# hello-world.net
KiCad netlist of a schematic drawn in EAGLE
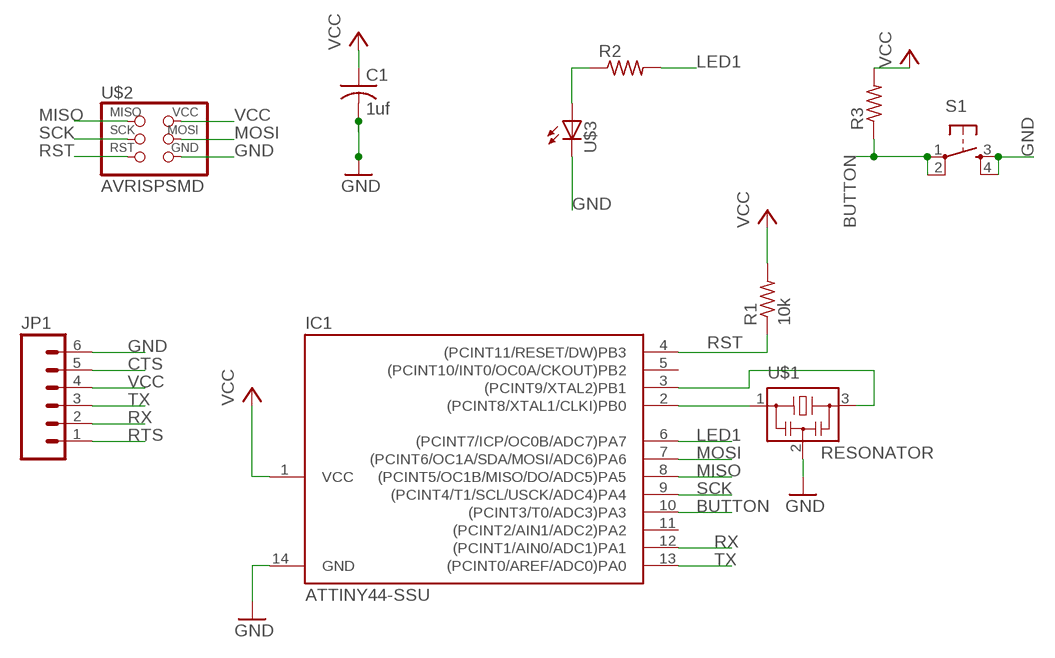
[diagram p0: schematic, sheet 1]

(export (version "E")
  (design (tool "Eeschema 10.0.6"))
  (components
    (comp (ref "C1")
      (value "1uf")
      (footprint "eagle-import:C1206")
      (libsource (lib "eagle-import") (part "C-USC1206"))
    )
    (comp (ref "IC1")
      (value "ATTINY44-SSU")
      (footprint "eagle-import:SOIC14")
      (libsource (lib "eagle-import") (part "ATTINY44-SSU"))
    )
    (comp (ref "JP1")
      (value "M06SMD")
      (footprint "eagle-import:1X06-SMD")
      (libsource (lib "eagle-import") (part "M06SMD"))
    )
    (comp (ref "R1")
      (value "10k")
      (footprint "eagle-import:R1206")
      (libsource (lib "eagle-import") (part "R-US_R1206"))
    )
    (comp (ref "R2")
      (value "RESISTOR1206")
      (footprint "eagle-import:1206")
      (libsource (lib "eagle-import") (part "RESISTOR1206"))
    )
    (comp (ref "R3")
      (value "RESISTOR1206")
      (footprint "eagle-import:1206")
      (libsource (lib "eagle-import") (part "RESISTOR1206"))
    )
    (comp (ref "S1")
      (value "6MM_SWITCH6MM_SWITCH")
      (footprint "eagle-import:6MM_SWITCH")
      (libsource (lib "eagle-import") (part "6MM_SWITCH6MM_SWITCH"))
    )
    (comp (ref "U$1")
      (value "RESONATOR")
      (footprint "eagle-import:EFOBM")
      (libsource (lib "eagle-import") (part "RESONATOR"))
    )
    (comp (ref "U$2")
      (value "AVRISPSMD")
      (footprint "eagle-import:2X03SMD")
      (libsource (lib "eagle-import") (part "AVRISPSMD"))
    )
    (comp (ref "U$3")
      (value "LED1206")
      (footprint "eagle-import:1206")
      (libsource (lib "eagle-import") (part "LED1206"))
    )
  )
  (nets
    (net (code "1") (name "/BUTTON") (class "Default")
      (node (ref "IC1") (pin "10") (pinfunction "(PCINT3/T0/ADC3)PA3_10") (pintype "bidirectional"))
      (node (ref "R3") (pin "1") (pinfunction "1_1") (pintype "passive"))
      (node (ref "S1") (pin "1") (pinfunction "P_1") (pintype "passive"))
      (node (ref "S1") (pin "2") (pinfunction "P1_2") (pintype "passive"))
    )
    (net (code "2") (name "/CTS") (class "Default")
      (node (ref "JP1") (pin "5") (pinfunction "5_5") (pintype "passive"))
    )
    (net (code "3") (name "/LED1") (class "Default")
      (node (ref "IC1") (pin "6") (pinfunction "(PCINT7/ICP/OC0B/ADC7)PA7_6") (pintype "bidirectional"))
      (node (ref "R2") (pin "2") (pinfunction "2_2") (pintype "passive"))
    )
    (net (code "4") (name "/MISO") (class "Default")
      (node (ref "IC1") (pin "8") (pinfunction "(PCINT5/OC1B/MISO/DO/ADC5)PA5_8") (pintype "bidirectional"))
      (node (ref "U$2") (pin "1") (pinfunction "MISO_1") (pintype "passive"))
    )
    (net (code "5") (name "/MOSI") (class "Default")
      (node (ref "IC1") (pin "7") (pinfunction "(PCINT6/OC1A/SDA/MOSI/ADC6)PA6_7") (pintype "bidirectional"))
      (node (ref "U$2") (pin "4") (pinfunction "MOSI_4") (pintype "passive"))
    )
    (net (code "6") (name "/RST") (class "Default")
      (node (ref "IC1") (pin "4") (pinfunction "(PCINT11/RESET/DW)PB3_4") (pintype "bidirectional"))
      (node (ref "R1") (pin "1") (pinfunction "1_1") (pintype "passive"))
      (node (ref "U$2") (pin "5") (pinfunction "RST_5") (pintype "passive"))
    )
    (net (code "7") (name "/RTS") (class "Default")
      (node (ref "JP1") (pin "1") (pinfunction "1_1") (pintype "passive"))
    )
    (net (code "8") (name "/RX") (class "Default")
      (node (ref "IC1") (pin "12") (pinfunction "(PCINT1/AIN0/ADC1)PA1_12") (pintype "bidirectional"))
      (node (ref "JP1") (pin "2") (pinfunction "2_2") (pintype "passive"))
    )
    (net (code "9") (name "/SCK") (class "Default")
      (node (ref "IC1") (pin "9") (pinfunction "(PCINT4/T1/SCL/USCK/ADC4)PA4_9") (pintype "bidirectional"))
      (node (ref "U$2") (pin "3") (pinfunction "SCK_3") (pintype "passive"))
    )
    (net (code "10") (name "/TX") (class "Default")
      (node (ref "IC1") (pin "13") (pinfunction "(PCINT0/AREF/ADC0)PA0_13") (pintype "bidirectional"))
      (node (ref "JP1") (pin "3") (pinfunction "3_3") (pintype "passive"))
    )
    (net (code "11") (name "GND") (class "Default")
      (node (ref "C1") (pin "2") (pinfunction "2_2") (pintype "passive"))
      (node (ref "IC1") (pin "14") (pinfunction "GND_14") (pintype "power_in"))
      (node (ref "JP1") (pin "6") (pinfunction "6_6") (pintype "passive"))
      (node (ref "S1") (pin "3") (pinfunction "S_3") (pintype "passive"))
      (node (ref "S1") (pin "4") (pinfunction "S1_4") (pintype "passive"))
      (node (ref "U$1") (pin "2") (pinfunction "2_2") (pintype "passive"))
      (node (ref "U$2") (pin "6") (pinfunction "GND_6") (pintype "passive"))
      (node (ref "U$3") (pin "2") (pinfunction "C_2") (pintype "passive"))
    )
    (net (code "12") (name "Net-(IC1-(PCINT8{slash}XTAL1{slash}CLKI)PB0)") (class "Default")
      (node (ref "IC1") (pin "2") (pinfunction "(PCINT8/XTAL1/CLKI)PB0_2") (pintype "bidirectional"))
      (node (ref "U$1") (pin "1") (pinfunction "1_1") (pintype "passive"))
    )
    (net (code "13") (name "Net-(IC1-(PCINT9{slash}XTAL2)PB1)") (class "Default")
      (node (ref "IC1") (pin "3") (pinfunction "(PCINT9/XTAL2)PB1_3") (pintype "bidirectional"))
      (node (ref "U$1") (pin "3") (pinfunction "3_3") (pintype "passive"))
    )
    (net (code "14") (name "Net-(U$3-A)") (class "Default")
      (node (ref "R2") (pin "1") (pinfunction "1_1") (pintype "passive"))
      (node (ref "U$3") (pin "1") (pinfunction "A_1") (pintype "passive"))
    )
    (net (code "15") (name "VCC") (class "Default")
      (node (ref "C1") (pin "1") (pinfunction "1_1") (pintype "passive"))
      (node (ref "IC1") (pin "1") (pinfunction "VCC_1") (pintype "power_in"))
      (node (ref "JP1") (pin "4") (pinfunction "4_4") (pintype "passive"))
      (node (ref "R1") (pin "2") (pinfunction "2_2") (pintype "passive"))
      (node (ref "R3") (pin "2") (pinfunction "2_2") (pintype "passive"))
      (node (ref "U$2") (pin "2") (pinfunction "VCC_2") (pintype "passive"))
    )
    (net (code "16") (name "unconnected-(IC1-(PCINT2{slash}AIN1{slash}ADC2)PA2-Pad11)") (class "Default")
      (node (ref "IC1") (pin "11") (pinfunction "(PCINT2/AIN1/ADC2)PA2_11") (pintype "bidirectional"))
    )
    (net (code "17") (name "unconnected-(IC1-(PCINT10{slash}INT0{slash}OC0A{slash}CKOUT)PB2-Pad5)") (class "Default")
      (node (ref "IC1") (pin "5") (pinfunction "(PCINT10/INT0/OC0A/CKOUT)PB2_5") (pintype "bidirectional"))
    )
  )
)
